# STM32.net
KiCad netlist of a schematic drawn in Altium Designer
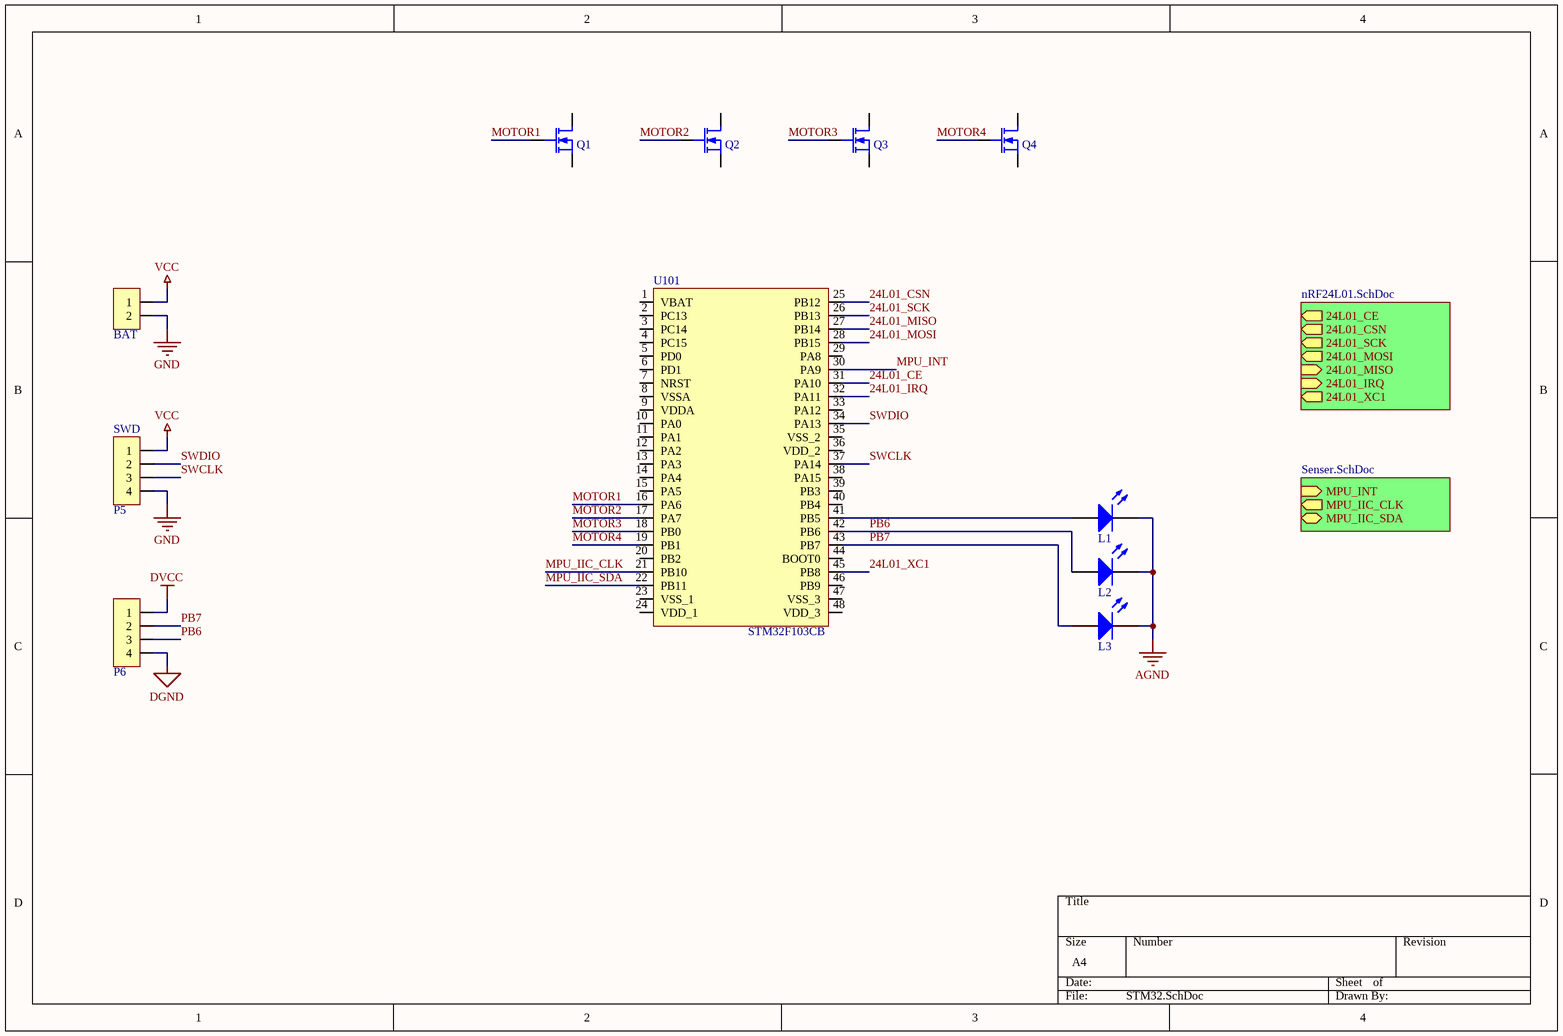
[diagram p0: STM32.SchDoc]

(export (version "E")
  (design (tool "Eeschema 10.0.6"))
  (components
    (comp (ref "BAT")
      (value "Port2")
      (description "PowerSupply")
      (libsource (lib "Quadcopter") (part "Port2"))
    )
    (comp (ref "L1") (value "LED") (libsource (lib "Quadcopter") (part "LED")))
    (comp (ref "L2") (value "LED") (libsource (lib "Quadcopter") (part "LED")))
    (comp (ref "L3") (value "LED") (libsource (lib "Quadcopter") (part "LED")))
    (comp (ref "P5") (value "SWD") (libsource (lib "Quadcopter") (part "Port4")))
    (comp (ref "P6") (value "Port4") (libsource (lib "Quadcopter") (part "Port4")))
    (comp (ref "Q1") (value "PWV31XN") (libsource (lib "Quadcopter") (part "PWV31XN")))
    (comp (ref "Q2") (value "PWV31XN") (libsource (lib "Quadcopter") (part "PWV31XN")))
    (comp (ref "Q3") (value "PWV31XN") (libsource (lib "Quadcopter") (part "PWV31XN")))
    (comp (ref "Q4") (value "PWV31XN") (libsource (lib "Quadcopter") (part "PWV31XN")))
    (comp (ref "U101") (value "STM32F103CB") (libsource (lib "Quadcopter") (part "STM32F103C8{backslash}CB")))
  )
  (nets
    (net (code "1") (name "/24L01_CE") (class "Default")
      (node (ref "U101") (pin "31") (pinfunction "PA10_31") (pintype "passive"))
    )
    (net (code "3") (name "/24L01_CSN") (class "Default")
      (node (ref "U101") (pin "25") (pinfunction "PB12_25") (pintype "passive"))
    )
    (net (code "5") (name "/24L01_IRQ") (class "Default")
      (node (ref "U101") (pin "32") (pinfunction "PA11_32") (pintype "passive"))
    )
    (net (code "7") (name "/24L01_MISO") (class "Default")
      (node (ref "U101") (pin "27") (pinfunction "PB14_27") (pintype "passive"))
    )
    (net (code "9") (name "/24L01_MOSI") (class "Default")
      (node (ref "U101") (pin "28") (pinfunction "PB15_28") (pintype "passive"))
    )
    (net (code "11") (name "/24L01_SCK") (class "Default")
      (node (ref "U101") (pin "26") (pinfunction "PB13_26") (pintype "passive"))
    )
    (net (code "13") (name "/24L01_XC1") (class "Default")
      (node (ref "U101") (pin "45") (pinfunction "PB8_45") (pintype "passive"))
    )
    (net (code "15") (name "/MOTOR1") (class "Default")
      (node (ref "Q1") (pin "2") (pinfunction "G_2") (pintype "passive"))
      (node (ref "U101") (pin "16") (pinfunction "PA6_16") (pintype "passive"))
    )
    (net (code "16") (name "/MOTOR2") (class "Default")
      (node (ref "Q2") (pin "2") (pinfunction "G_2") (pintype "passive"))
      (node (ref "U101") (pin "17") (pinfunction "PA7_17") (pintype "passive"))
    )
    (net (code "17") (name "/MOTOR3") (class "Default")
      (node (ref "Q3") (pin "2") (pinfunction "G_2") (pintype "passive"))
      (node (ref "U101") (pin "18") (pinfunction "PB0_18") (pintype "passive"))
    )
    (net (code "18") (name "/MOTOR4") (class "Default")
      (node (ref "Q4") (pin "2") (pinfunction "G_2") (pintype "passive"))
      (node (ref "U101") (pin "19") (pinfunction "PB1_19") (pintype "passive"))
    )
    (net (code "19") (name "/MPU_IIC_CLK") (class "Default")
      (node (ref "U101") (pin "21") (pinfunction "PB10_21") (pintype "passive"))
    )
    (net (code "21") (name "/MPU_IIC_SDA") (class "Default")
      (node (ref "U101") (pin "22") (pinfunction "PB11_22") (pintype "passive"))
    )
    (net (code "23") (name "/MPU_INT") (class "Default")
      (node (ref "U101") (pin "30") (pinfunction "PA9_30") (pintype "passive"))
    )
    (net (code "25") (name "/PB6") (class "Default")
      (node (ref "L2") (pin "1") (pinfunction "A_1") (pintype "passive"))
      (node (ref "P6") (pin "3") (pinfunction "3_3") (pintype "passive"))
      (node (ref "U101") (pin "42") (pinfunction "PB6_42") (pintype "passive"))
    )
    (net (code "26") (name "/PB7") (class "Default")
      (node (ref "L3") (pin "1") (pinfunction "A_1") (pintype "passive"))
      (node (ref "P6") (pin "2") (pinfunction "2_2") (pintype "passive"))
      (node (ref "U101") (pin "43") (pinfunction "PB7_43") (pintype "passive"))
    )
    (net (code "27") (name "/SWCLK") (class "Default")
      (node (ref "P5") (pin "3") (pinfunction "3_3") (pintype "passive"))
      (node (ref "U101") (pin "37") (pinfunction "PA14_37") (pintype "passive"))
    )
    (net (code "28") (name "/SWDIO") (class "Default")
      (node (ref "P5") (pin "2") (pinfunction "2_2") (pintype "passive"))
      (node (ref "U101") (pin "34") (pinfunction "PA13_34") (pintype "passive"))
    )
    (net (code "29") (name "AGND") (class "Default")
      (node (ref "L1") (pin "2") (pinfunction "K_2") (pintype "passive"))
      (node (ref "L2") (pin "2") (pinfunction "K_2") (pintype "passive"))
      (node (ref "L3") (pin "2") (pinfunction "K_2") (pintype "passive"))
    )
    (net (code "30") (name "DGND") (class "Default")
      (node (ref "P6") (pin "4") (pinfunction "4_4") (pintype "passive"))
    )
    (net (code "31") (name "DVCC") (class "Default")
      (node (ref "P6") (pin "1") (pinfunction "1_1") (pintype "passive"))
    )
    (net (code "32") (name "GND") (class "Default")
      (node (ref "BAT") (pin "2") (pinfunction "2_2") (pintype "passive"))
      (node (ref "P5") (pin "4") (pinfunction "4_4") (pintype "passive"))
    )
    (net (code "33") (name "Net-(L1-A)") (class "Default")
      (node (ref "L1") (pin "1") (pinfunction "A_1") (pintype "passive"))
      (node (ref "U101") (pin "41") (pinfunction "PB5_41") (pintype "passive"))
    )
    (net (code "34") (name "VCC") (class "Default")
      (node (ref "BAT") (pin "1") (pinfunction "1_1") (pintype "passive"))
      (node (ref "P5") (pin "1") (pinfunction "1_1") (pintype "passive"))
    )
    (net (code "35") (name "unconnected-(Q1-D-Pad1)") (class "Default")
      (node (ref "Q1") (pin "1") (pinfunction "D_1") (pintype "passive"))
    )
    (net (code "36") (name "unconnected-(Q1-S-Pad3)") (class "Default")
      (node (ref "Q1") (pin "3") (pinfunction "S_3") (pintype "passive"))
    )
    (net (code "37") (name "unconnected-(Q2-D-Pad1)") (class "Default")
      (node (ref "Q2") (pin "1") (pinfunction "D_1") (pintype "passive"))
    )
    (net (code "38") (name "unconnected-(Q2-S-Pad3)") (class "Default")
      (node (ref "Q2") (pin "3") (pinfunction "S_3") (pintype "passive"))
    )
    (net (code "39") (name "unconnected-(Q3-D-Pad1)") (class "Default")
      (node (ref "Q3") (pin "1") (pinfunction "D_1") (pintype "passive"))
    )
    (net (code "40") (name "unconnected-(Q3-S-Pad3)") (class "Default")
      (node (ref "Q3") (pin "3") (pinfunction "S_3") (pintype "passive"))
    )
    (net (code "41") (name "unconnected-(Q4-D-Pad1)") (class "Default")
      (node (ref "Q4") (pin "1") (pinfunction "D_1") (pintype "passive"))
    )
    (net (code "42") (name "unconnected-(Q4-S-Pad3)") (class "Default")
      (node (ref "Q4") (pin "3") (pinfunction "S_3") (pintype "passive"))
    )
    (net (code "43") (name "unconnected-(U101-BOOT0-Pad44)") (class "Default")
      (node (ref "U101") (pin "44") (pinfunction "BOOT0_44") (pintype "passive"))
    )
    (net (code "44") (name "unconnected-(U101-NRST-Pad7)") (class "Default")
      (node (ref "U101") (pin "7") (pinfunction "NRST_7") (pintype "passive"))
    )
    (net (code "45") (name "unconnected-(U101-PA0-Pad10)") (class "Default")
      (node (ref "U101") (pin "10") (pinfunction "PA0_10") (pintype "passive"))
    )
    (net (code "46") (name "unconnected-(U101-PA1-Pad11)") (class "Default")
      (node (ref "U101") (pin "11") (pinfunction "PA1_11") (pintype "passive"))
    )
    (net (code "47") (name "unconnected-(U101-PA2-Pad12)") (class "Default")
      (node (ref "U101") (pin "12") (pinfunction "PA2_12") (pintype "passive"))
    )
    (net (code "48") (name "unconnected-(U101-PA3-Pad13)") (class "Default")
      (node (ref "U101") (pin "13") (pinfunction "PA3_13") (pintype "passive"))
    )
    (net (code "49") (name "unconnected-(U101-PA4-Pad14)") (class "Default")
      (node (ref "U101") (pin "14") (pinfunction "PA4_14") (pintype "passive"))
    )
    (net (code "50") (name "unconnected-(U101-PA5-Pad15)") (class "Default")
      (node (ref "U101") (pin "15") (pinfunction "PA5_15") (pintype "passive"))
    )
    (net (code "51") (name "unconnected-(U101-PA8-Pad29)") (class "Default")
      (node (ref "U101") (pin "29") (pinfunction "PA8_29") (pintype "passive"))
    )
    (net (code "52") (name "unconnected-(U101-PA12-Pad33)") (class "Default")
      (node (ref "U101") (pin "33") (pinfunction "PA12_33") (pintype "passive"))
    )
    (net (code "53") (name "unconnected-(U101-PA15-Pad38)") (class "Default")
      (node (ref "U101") (pin "38") (pinfunction "PA15_38") (pintype "passive"))
    )
    (net (code "54") (name "unconnected-(U101-PB2-Pad20)") (class "Default")
      (node (ref "U101") (pin "20") (pinfunction "PB2_20") (pintype "passive"))
    )
    (net (code "55") (name "unconnected-(U101-PB3-Pad39)") (class "Default")
      (node (ref "U101") (pin "39") (pinfunction "PB3_39") (pintype "passive"))
    )
    (net (code "56") (name "unconnected-(U101-PB4-Pad40)") (class "Default")
      (node (ref "U101") (pin "40") (pinfunction "PB4_40") (pintype "passive"))
    )
    (net (code "57") (name "unconnected-(U101-PB9-Pad46)") (class "Default")
      (node (ref "U101") (pin "46") (pinfunction "PB9_46") (pintype "passive"))
    )
    (net (code "58") (name "unconnected-(U101-PC13-Pad2)") (class "Default")
      (node (ref "U101") (pin "2") (pinfunction "PC13_2") (pintype "passive"))
    )
    (net (code "59") (name "unconnected-(U101-PC14-Pad3)") (class "Default")
      (node (ref "U101") (pin "3") (pinfunction "PC14_3") (pintype "passive"))
    )
    (net (code "60") (name "unconnected-(U101-PC15-Pad4)") (class "Default")
      (node (ref "U101") (pin "4") (pinfunction "PC15_4") (pintype "passive"))
    )
    (net (code "61") (name "unconnected-(U101-PD0-Pad5)") (class "Default")
      (node (ref "U101") (pin "5") (pinfunction "PD0_5") (pintype "passive"))
    )
    (net (code "62") (name "unconnected-(U101-PD1-Pad6)") (class "Default")
      (node (ref "U101") (pin "6") (pinfunction "PD1_6") (pintype "passive"))
    )
    (net (code "63") (name "unconnected-(U101-VBAT-Pad1)") (class "Default")
      (node (ref "U101") (pin "1") (pinfunction "VBAT_1") (pintype "passive"))
    )
    (net (code "64") (name "unconnected-(U101-VDDA-Pad9)") (class "Default")
      (node (ref "U101") (pin "9") (pinfunction "VDDA_9") (pintype "passive"))
    )
    (net (code "65") (name "unconnected-(U101-VDD_1-Pad24)") (class "Default")
      (node (ref "U101") (pin "24") (pinfunction "VDD_1_24") (pintype "passive"))
    )
    (net (code "66") (name "unconnected-(U101-VDD_2-Pad36)") (class "Default")
      (node (ref "U101") (pin "36") (pinfunction "VDD_2_36") (pintype "passive"))
    )
    (net (code "67") (name "unconnected-(U101-VDD_3-Pad48)") (class "Default")
      (node (ref "U101") (pin "48") (pinfunction "VDD_3_48") (pintype "passive"))
    )
    (net (code "68") (name "unconnected-(U101-VSSA-Pad8)") (class "Default")
      (node (ref "U101") (pin "8") (pinfunction "VSSA_8") (pintype "passive"))
    )
    (net (code "69") (name "unconnected-(U101-VSS_1-Pad23)") (class "Default")
      (node (ref "U101") (pin "23") (pinfunction "VSS_1_23") (pintype "passive"))
    )
    (net (code "70") (name "unconnected-(U101-VSS_2-Pad35)") (class "Default")
      (node (ref "U101") (pin "35") (pinfunction "VSS_2_35") (pintype "passive"))
    )
    (net (code "71") (name "unconnected-(U101-VSS_3-Pad47)") (class "Default")
      (node (ref "U101") (pin "47") (pinfunction "VSS_3_47") (pintype "passive"))
    )
  )
)
